# ESPEED32_V03.net
KiCad netlist of a schematic drawn in Altium Designer
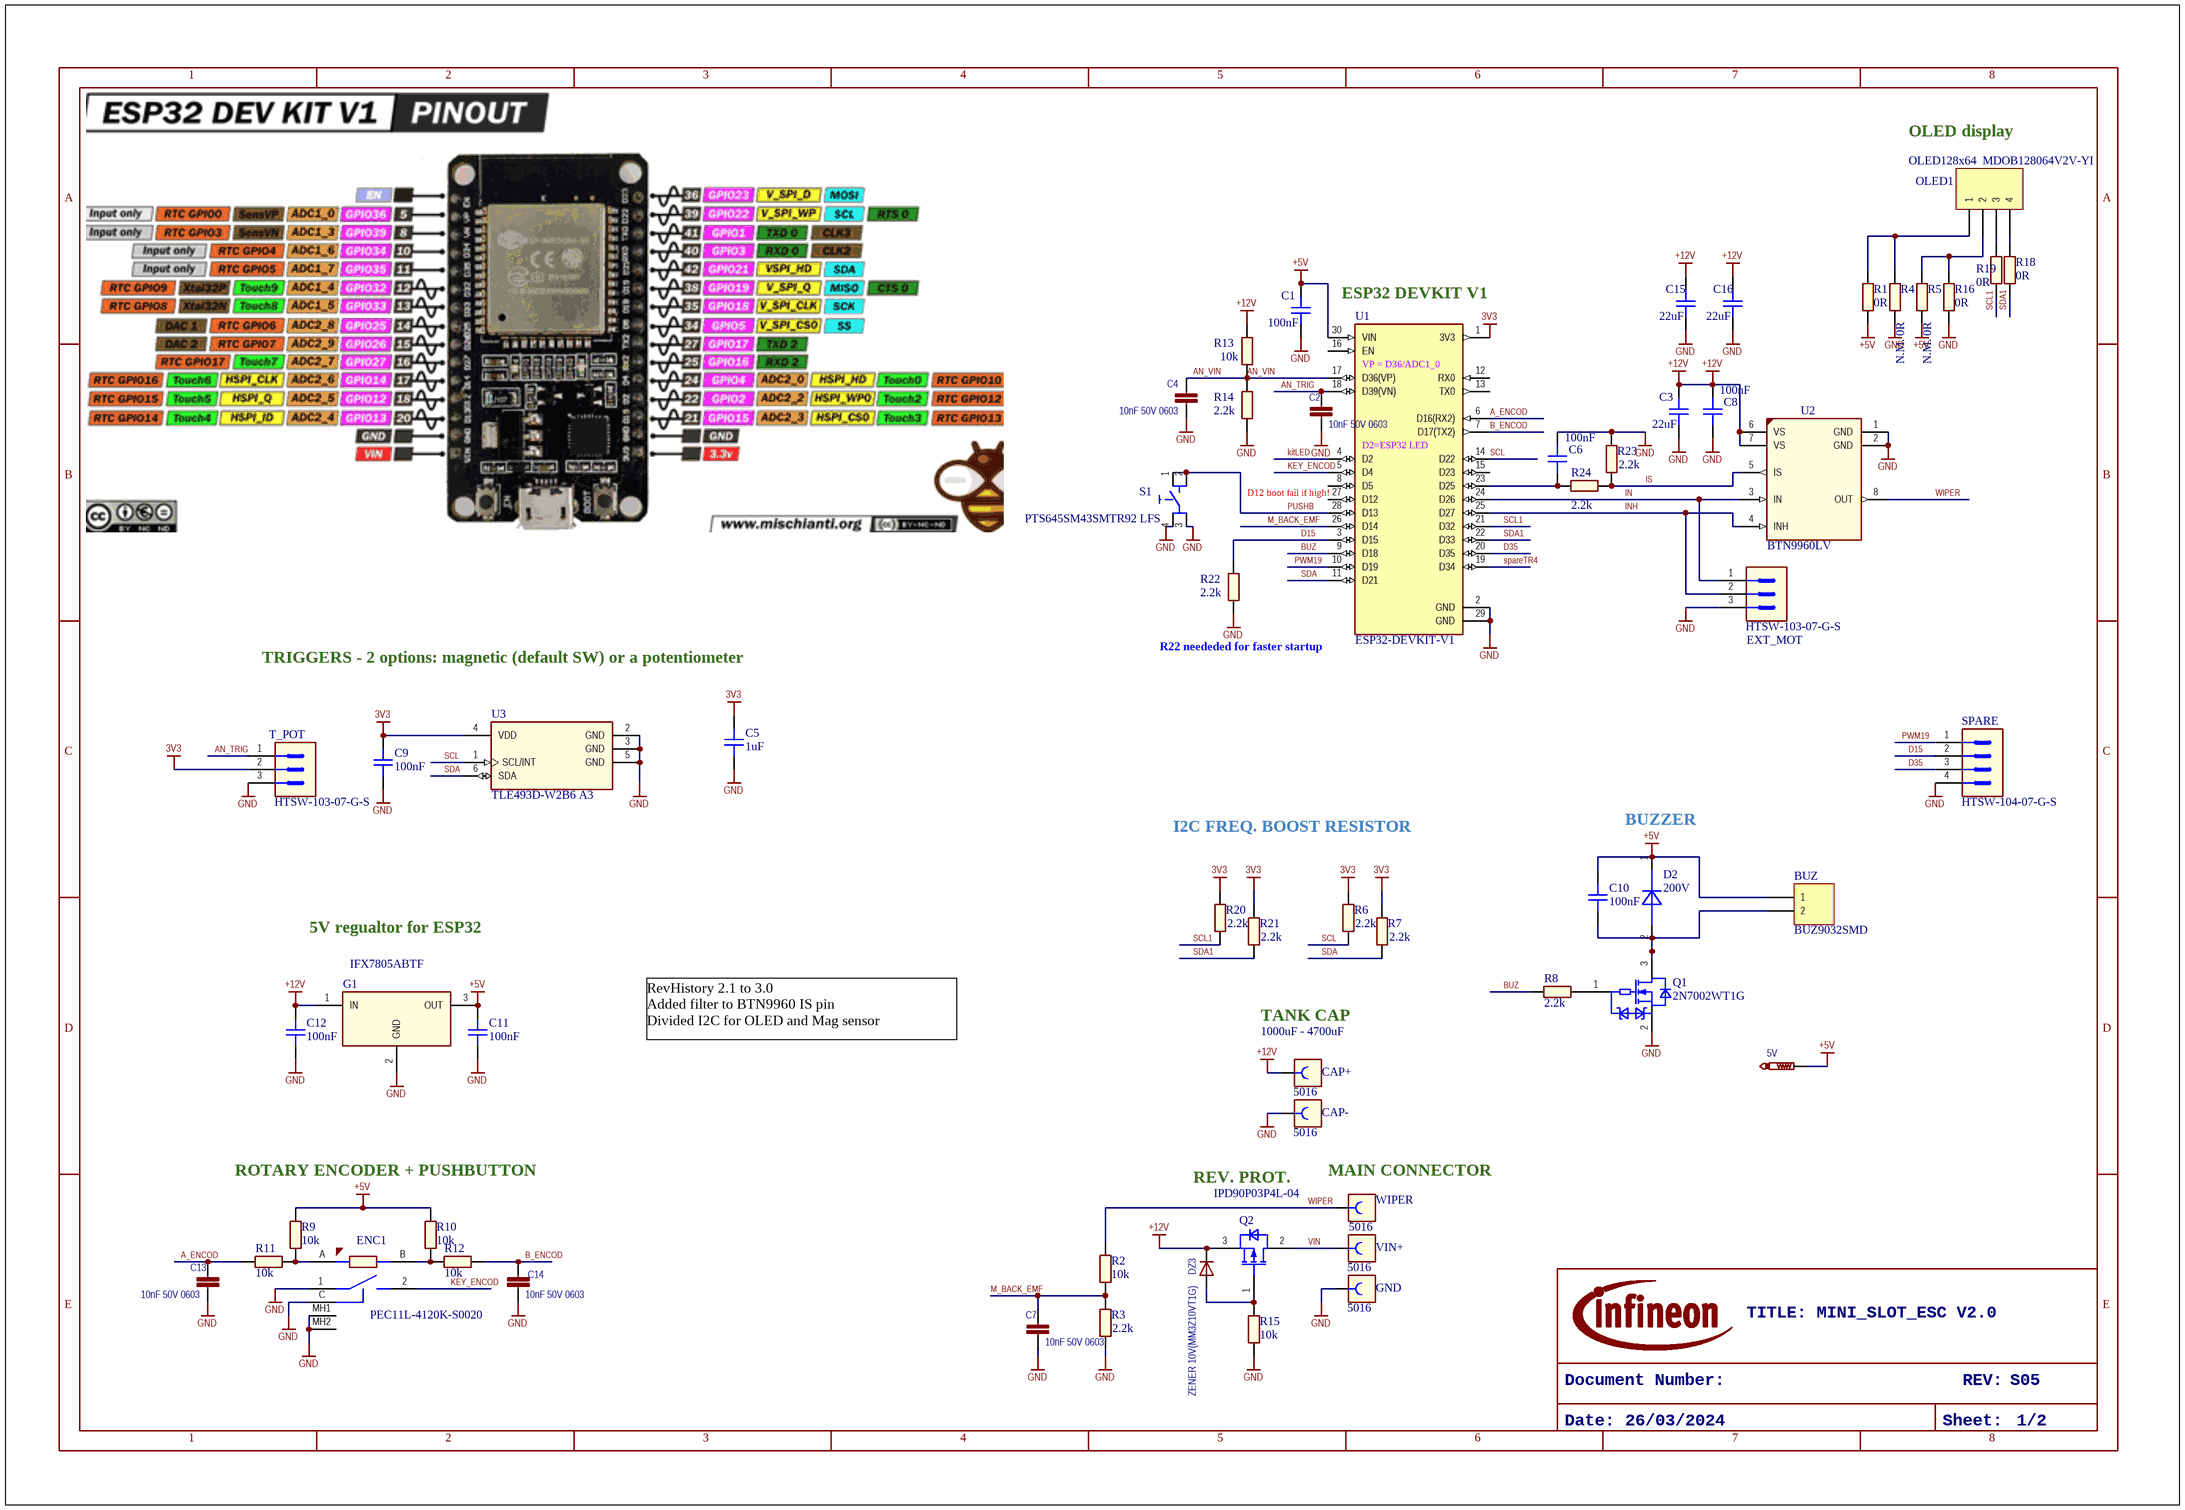
[diagram p0: ESPEED32_V03.SchDoc]

(export (version "E")
  (design (tool "Eeschema 10.0.6"))
  (components
    (comp (ref "5V")
      (value "NO_POP_Mill-Max 2501-2-00-80-00-00-07-0")
      (footprint "TEST POINT MILL-MAX 2501-2-00-80-00-00-07-0")
      (description "testpad 1mm diameter")
      (libsource (lib "LitixFlexArkasMultiChDemo3") (part "TESTPAD_1MM"))
    )
    (comp (ref "BUZ")
      (value "BUZ9032SMD")
      (footprint "MF_SLOT_ESC_V2.0:BUZ9032_SMD")
      (description "Header, 2-Pin")
      (fields (field (name "PUBLISHER") "Altium Limited"))
      (libsource (lib "Miscellaneous Connectors") (part "Header 2"))
    )
    (comp (ref "C1")
      (value "100nF")
      (footprint "C0603")
      (description "CAP / CERA / 100nF / 25V / 10% / X8R (EIA) / -55°C to 150°C / 0603(1608) / SMD / -")
      (fields (field (name "LEGACY PARTNUMBER") "CAP01008841") (field (name "MANUFACTURER") "MuRata"))
      (libsource (lib "PCBLibraryData") (part "CAP-SGL-STD-02P_00000001"))
    )
    (comp (ref "C2")
      (value "10nF 50V 0603")
      (footprint "C0603")
      (description "CAPACITOR, European symbol")
      (libsource (lib "rcl") (part "C-EUC0402"))
    )
    (comp (ref "C3")
      (value "22uF")
      (footprint "CAPC3225X270N")
      (description "CAP / CERA / 22uF / 25V / 20% / X5R (EIA) / -55°C to 85°C / 1210(3225) / SMD / -")
      (fields (field (name "LEGACY PARTNUMBER") "CAP01005898") (field (name "MANUFACTURER") "MuRata"))
      (libsource (lib "PCBLibraryData") (part "CAP-SGL-STD-02P_00000001"))
    )
    (comp (ref "C4")
      (value "10nF 50V 0603")
      (footprint "C0603")
      (description "CAPACITOR, European symbol")
      (libsource (lib "rcl") (part "C-EUC0402"))
    )
    (comp (ref "C5")
      (value "1uF")
      (footprint "CAPC1608X87N-1")
      (description "CAP / CERA / 1uF / 25V / 20% / X5R (EIA) / -55°C to 85°C / 0603(1608) / SMD / -")
      (fields (field (name "MANUFACTURER") "Wurth Elektronik"))
      (libsource (lib "PCBLibraryData") (part "CAP-SGL-STD-02P_00000001"))
    )
    (comp (ref "C6")
      (value "100nF")
      (footprint "C0603")
      (description "CAP / CERA / 100nF / 25V / 10% / X8R (EIA) / -55°C to 150°C / 0603(1608) / SMD / -")
      (fields (field (name "LEGACY PARTNUMBER") "CAP01008841") (field (name "MANUFACTURER") "MuRata"))
      (libsource (lib "PCBLibraryData") (part "CAP-SGL-STD-02P_00000001"))
    )
    (comp (ref "C7")
      (value "10nF 50V 0603")
      (footprint "C0603")
      (description "CAPACITOR, European symbol")
      (libsource (lib "rcl") (part "C-EUC0402"))
    )
    (comp (ref "C8")
      (value "100nF")
      (footprint "C0603")
      (description "CAP / CERA / 100nF / 25V / 10% / X8R (EIA) / -55°C to 150°C / 0603(1608) / SMD / -")
      (fields (field (name "LEGACY PARTNUMBER") "CAP01008841") (field (name "MANUFACTURER") "MuRata"))
      (libsource (lib "PCBLibraryData") (part "CAP-SGL-STD-02P_00000001"))
    )
    (comp (ref "C9")
      (value "100nF")
      (footprint "C0603")
      (description "CAP / CERA / 100nF / 25V / 10% / X8R (EIA) / -55°C to 150°C / 0603(1608) / SMD / -")
      (fields (field (name "LEGACY PARTNUMBER") "CAP01008841") (field (name "MANUFACTURER") "MuRata"))
      (libsource (lib "PCBLibraryData") (part "CAP-SGL-STD-02P_00000001"))
    )
    (comp (ref "C10")
      (value "100nF")
      (footprint "C0603")
      (description "CAP / CERA / 100nF / 25V / 10% / X8R (EIA) / -55°C to 150°C / 0603(1608) / SMD / -")
      (fields (field (name "LEGACY PARTNUMBER") "CAP01008841") (field (name "MANUFACTURER") "MuRata"))
      (libsource (lib "PCBLibraryData") (part "CAP-SGL-STD-02P_00000001"))
    )
    (comp (ref "C11")
      (value "100nF")
      (footprint "C0603")
      (description "CAP / CERA / 100nF / 25V / 10% / X8R (EIA) / -55°C to 150°C / 0603(1608) / SMD / -")
      (fields (field (name "LEGACY PARTNUMBER") "CAP01008841") (field (name "MANUFACTURER") "MuRata"))
      (libsource (lib "PCBLibraryData") (part "CAP-SGL-STD-02P_00000001"))
    )
    (comp (ref "C12")
      (value "100nF")
      (footprint "C0603")
      (description "CAP / CERA / 100nF / 25V / 10% / X8R (EIA) / -55°C to 150°C / 0603(1608) / SMD / -")
      (fields (field (name "LEGACY PARTNUMBER") "CAP01008841") (field (name "MANUFACTURER") "MuRata"))
      (libsource (lib "PCBLibraryData") (part "CAP-SGL-STD-02P_00000001"))
    )
    (comp (ref "C13")
      (value "10nF 50V 0603")
      (footprint "C0603")
      (description "CAPACITOR, European symbol")
      (libsource (lib "rcl") (part "C-EUC0402"))
    )
    (comp (ref "C14")
      (value "10nF 50V 0603")
      (footprint "C0603")
      (description "CAPACITOR, European symbol")
      (libsource (lib "rcl") (part "C-EUC0402"))
    )
    (comp (ref "C15")
      (value "22uF")
      (footprint "CAPC3225X270N")
      (description "CAP / CERA / 22uF / 25V / 20% / X5R (EIA) / -55°C to 85°C / 1210(3225) / SMD / -")
      (fields (field (name "LEGACY PARTNUMBER") "CAP01005898") (field (name "MANUFACTURER") "MuRata"))
      (libsource (lib "PCBLibraryData") (part "CAP-SGL-STD-02P_00000001"))
    )
    (comp (ref "C16")
      (value "22uF")
      (footprint "CAPC3225X270N")
      (description "CAP / CERA / 22uF / 25V / 20% / X5R (EIA) / -55°C to 85°C / 1210(3225) / SMD / -")
      (fields (field (name "LEGACY PARTNUMBER") "CAP01005898") (field (name "MANUFACTURER") "MuRata"))
      (libsource (lib "PCBLibraryData") (part "CAP-SGL-STD-02P_00000001"))
    )
    (comp (ref "CAP+")
      (value "5016")
      (footprint "CON-SMD-TP-5016")
      (description "Test Point, Compact, Surface Mount, Finish- Silver Plate")
      (fields
        (field (name "LEGACY PARTNUMBER") "CON01501019")
        (field (name "MANUFACTURER") "Keystone Electronics Corp.")
      )
      (libsource (lib "PCBLibraryData") (part "connector_1_f"))
    )
    (comp (ref "CAP-")
      (value "5016")
      (footprint "CON-SMD-TP-5016")
      (description "Test Point, Compact, Surface Mount, Finish- Silver Plate")
      (fields
        (field (name "LEGACY PARTNUMBER") "CON01501019")
        (field (name "MANUFACTURER") "Keystone Electronics Corp.")
      )
      (libsource (lib "PCBLibraryData") (part "connector_1_f"))
    )
    (comp (ref "D2")
      (value "200V")
      (footprint "DIO-SMD-RF05VYM2SFH")
      (description "Super Fast Recovery Diode")
      (fields (field (name "MANUFACTURER") "ROHM Semiconductors"))
      (libsource (lib "PCBLibraryData") (part "d_std_a"))
    )
    (comp (ref "DZ3")
      (value "ZENER 10V(MM3Z10VT1G)")
      (footprint "SOD323")
      (description "Zener 10V MM3Z10VST1G")
      (libsource (lib "000_Self_made_Gernot") (part "NXP_BAT46WJ"))
    )
    (comp (ref "ENC1")
      (value "PEC11L-4120K-S0020")
      (footprint "SW-THT-PEC11L-4XXXK-SXXXX")
      (description "11 mm Low Profile Encoder")
      (fields (field (name "MANUFACTURER") "Bourns"))
      (libsource (lib "PCBLibraryData") (part "PEC11L-4XXXK-SXXXX"))
    )
    (comp (ref "EXT_MOT")
      (value "HTSW-103-07-G-S")
      (footprint "CON-THT-2.54-3-1-8.38")
      (description "Through hole .025 SQ Post Header, 2.54mm pitch, 3 pin, vertical, single row")
      (fields (field (name "LEGACY PARTNUMBER") "CON00000054") (field (name "MANUFACTURER") "Samtec"))
      (libsource (lib "PCBLibraryData") (part "Header 3"))
    )
    (comp (ref "G1")
      (value "IFX7805ABTF")
      (footprint "TO228P998X235-3N-2-V")
      (description "Three Terminal 1.0A Positive Voltage Regulator")
      (fields
        (field (name "LEGACY PARTNUMBER") "IFX01400731")
        (field (name "MANUFACTURER") "Infineon Technologies")
      )
      (libsource (lib "PCBLibraryData") (part "IFX7805ABTX"))
    )
    (comp (ref "GND")
      (value "5016")
      (footprint "CON-SMD-TP-5016")
      (description "Test Point, Compact, Surface Mount, Finish- Silver Plate")
      (fields
        (field (name "LEGACY PARTNUMBER") "CON01501019")
        (field (name "MANUFACTURER") "Keystone Electronics Corp.")
      )
      (libsource (lib "PCBLibraryData") (part "connector_1_f"))
    )
    (comp (ref "OLED1")
      (value "OLED128x64  MDOB128064V2V-YI")
      (footprint "OLED 128X64 1.3\"")
      (description "Header, 4-Pin")
      (fields (field (name "PUBLISHER") "Altium Limited"))
      (libsource (lib "Miscellaneous Connectors") (part "Header 4"))
    )
    (comp (ref "Q1")
      (value "2N7002WT1G")
      (footprint "SOT65P220X100-3N")
      (fields (field (name "MANUFACTURER") "ON Semiconductor"))
      (libsource (lib "PCBLibraryData") (part "igfet_n_ch_enh_dio_r_g_esd_gs_1g2s3d_3p-2"))
    )
    (comp (ref "Q2")
      (value "IPD90P03P4L-04")
      (footprint "TO228P998X235-3N-2-V")
      (description "OptiMOS - P2 Power-Transistor, P-channel-Enhancement mode, VDS -30V")
      (fields
        (field (name "LEGACY PARTNUMBER") "IFX00200003")
        (field (name "MANUFACTURER") "Infineon Technologies")
      )
      (libsource (lib "PCBLibraryData") (part "igfet_p_ch_enh_dio_1g2d3s_3p"))
    )
    (comp (ref "R1")
      (value "0R")
      (footprint "R0603")
      (description "General Purpose Chip Resistor")
      (fields (field (name "LEGACY PARTNUMBER") "RES00000126") (field (name "MANUFACTURER") "Yageo"))
      (libsource (lib "TLD5542-1MultiCh_V4.3") (part "328011"))
    )
    (comp (ref "R2")
      (value "10k")
      (footprint "R0603")
      (description "RES / STD / 10k / 100mW / 5% / 100ppm/K / -55°C to 155°C / 0603(1608) / SMD / -")
      (fields (field (name "LEGACY PARTNUMBER") "RES01805989") (field (name "MANUFACTURER") "Yageo"))
      (libsource (lib "") (part "RES-SGL-STD-02P_00000006_1"))
    )
    (comp (ref "R3")
      (value "2.2k")
      (footprint "R0603")
      (description "RES / STD / 2.2k / 100mW / 1% / 100ppm/K / -55°C to 155°C / 0603(1608) / SMD / -")
      (fields (field (name "LEGACY PARTNUMBER") "RES00000093") (field (name "MANUFACTURER") "Yageo"))
      (libsource (lib "") (part "RES-SGL-STD-02P_00000006_1"))
    )
    (comp (ref "R4")
      (value "N.M. 0R")
      (footprint "R0603")
      (description "General Purpose Chip Resistor")
      (fields (field (name "LEGACY PARTNUMBER") "RES00000126") (field (name "MANUFACTURER") "Yageo"))
      (libsource (lib "TLD5542-1MultiCh_V4.3") (part "328011"))
    )
    (comp (ref "R5")
      (value "N.M. 0R")
      (footprint "R0603")
      (description "General Purpose Chip Resistor")
      (fields (field (name "LEGACY PARTNUMBER") "RES00000126") (field (name "MANUFACTURER") "Yageo"))
      (libsource (lib "TLD5542-1MultiCh_V4.3") (part "328011"))
    )
    (comp (ref "R6")
      (value "2.2k")
      (footprint "R0603")
      (description "RES / STD / 2.2k / 100mW / 1% / 100ppm/K / -55°C to 155°C / 0603(1608) / SMD / -")
      (fields (field (name "LEGACY PARTNUMBER") "RES00000093") (field (name "MANUFACTURER") "Yageo"))
      (libsource (lib "") (part "RES-SGL-STD-02P_00000006_1"))
    )
    (comp (ref "R7")
      (value "2.2k")
      (footprint "R0603")
      (description "RES / STD / 2.2k / 100mW / 1% / 100ppm/K / -55°C to 155°C / 0603(1608) / SMD / -")
      (fields (field (name "LEGACY PARTNUMBER") "RES00000093") (field (name "MANUFACTURER") "Yageo"))
      (libsource (lib "") (part "RES-SGL-STD-02P_00000006_1"))
    )
    (comp (ref "R8")
      (value "2.2k")
      (footprint "R0603")
      (description "RES / STD / 2.2k / 100mW / 1% / 100ppm/K / -55°C to 155°C / 0603(1608) / SMD / -")
      (fields (field (name "LEGACY PARTNUMBER") "RES00000093") (field (name "MANUFACTURER") "Yageo"))
      (libsource (lib "") (part "RES-SGL-STD-02P_00000006_2"))
    )
    (comp (ref "R9")
      (value "10k")
      (footprint "R0603")
      (description "RES / STD / 10k / 100mW / 5% / 100ppm/K / -55°C to 155°C / 0603(1608) / SMD / -")
      (fields (field (name "LEGACY PARTNUMBER") "RES01805989") (field (name "MANUFACTURER") "Yageo"))
      (libsource (lib "") (part "RES-SGL-STD-02P_00000006_1"))
    )
    (comp (ref "R10")
      (value "10k")
      (footprint "R0603")
      (description "RES / STD / 10k / 100mW / 5% / 100ppm/K / -55°C to 155°C / 0603(1608) / SMD / -")
      (fields (field (name "LEGACY PARTNUMBER") "RES01805989") (field (name "MANUFACTURER") "Yageo"))
      (libsource (lib "") (part "RES-SGL-STD-02P_00000006_1"))
    )
    (comp (ref "R11")
      (value "10k")
      (footprint "R0603")
      (description "RES / STD / 10k / 100mW / 5% / 100ppm/K / -55°C to 155°C / 0603(1608) / SMD / -")
      (fields (field (name "LEGACY PARTNUMBER") "RES01805989") (field (name "MANUFACTURER") "Yageo"))
      (libsource (lib "") (part "RES-SGL-STD-02P_00000006_2"))
    )
    (comp (ref "R12")
      (value "10k")
      (footprint "R0603")
      (description "RES / STD / 10k / 100mW / 5% / 100ppm/K / -55°C to 155°C / 0603(1608) / SMD / -")
      (fields (field (name "LEGACY PARTNUMBER") "RES01805989") (field (name "MANUFACTURER") "Yageo"))
      (libsource (lib "") (part "RES-SGL-STD-02P_00000006_2"))
    )
    (comp (ref "R13")
      (value "10k")
      (footprint "R0603")
      (description "RES / STD / 10k / 100mW / 5% / 100ppm/K / -55°C to 155°C / 0603(1608) / SMD / -")
      (fields (field (name "LEGACY PARTNUMBER") "RES01805989") (field (name "MANUFACTURER") "Yageo"))
      (libsource (lib "") (part "RES-SGL-STD-02P_00000006_1"))
    )
    (comp (ref "R14")
      (value "2.2k")
      (footprint "R0603")
      (description "RES / STD / 2.2k / 100mW / 1% / 100ppm/K / -55°C to 155°C / 0603(1608) / SMD / -")
      (fields (field (name "LEGACY PARTNUMBER") "RES00000093") (field (name "MANUFACTURER") "Yageo"))
      (libsource (lib "") (part "RES-SGL-STD-02P_00000006_1"))
    )
    (comp (ref "R15")
      (value "10k")
      (footprint "R0603")
      (description "RES / STD / 10k / 100mW / 5% / 100ppm/K / -55°C to 155°C / 0603(1608) / SMD / -")
      (fields (field (name "LEGACY PARTNUMBER") "RES01805989") (field (name "MANUFACTURER") "Yageo"))
      (libsource (lib "") (part "RES-SGL-STD-02P_00000006_1"))
    )
    (comp (ref "R16")
      (value "0R")
      (footprint "R0603")
      (description "General Purpose Chip Resistor")
      (fields (field (name "LEGACY PARTNUMBER") "RES00000126") (field (name "MANUFACTURER") "Yageo"))
      (libsource (lib "TLD5542-1MultiCh_V4.3") (part "328011"))
    )
    (comp (ref "R18")
      (value "0R")
      (footprint "R0603")
      (description "General Purpose Chip Resistor")
      (fields (field (name "LEGACY PARTNUMBER") "RES00000126") (field (name "MANUFACTURER") "Yageo"))
      (libsource (lib "TLD5542-1MultiCh_V4.3") (part "328011"))
    )
    (comp (ref "R19")
      (value "0R")
      (footprint "R0603")
      (description "General Purpose Chip Resistor")
      (fields (field (name "LEGACY PARTNUMBER") "RES00000126") (field (name "MANUFACTURER") "Yageo"))
      (libsource (lib "TLD5542-1MultiCh_V4.3") (part "328011"))
    )
    (comp (ref "R20")
      (value "2.2k")
      (footprint "R0603")
      (description "RES / STD / 2.2k / 100mW / 1% / 100ppm/K / -55°C to 155°C / 0603(1608) / SMD / -")
      (fields (field (name "LEGACY PARTNUMBER") "RES00000093") (field (name "MANUFACTURER") "Yageo"))
      (libsource (lib "") (part "RES-SGL-STD-02P_00000006_1"))
    )
    (comp (ref "R21")
      (value "2.2k")
      (footprint "R0603")
      (description "RES / STD / 2.2k / 100mW / 1% / 100ppm/K / -55°C to 155°C / 0603(1608) / SMD / -")
      (fields (field (name "LEGACY PARTNUMBER") "RES00000093") (field (name "MANUFACTURER") "Yageo"))
      (libsource (lib "") (part "RES-SGL-STD-02P_00000006_1"))
    )
    (comp (ref "R22")
      (value "2.2k")
      (footprint "R0603")
      (description "RES / STD / 2.2k / 100mW / 1% / 100ppm/K / -55°C to 155°C / 0603(1608) / SMD / -")
      (fields (field (name "LEGACY PARTNUMBER") "RES00000093") (field (name "MANUFACTURER") "Yageo"))
      (libsource (lib "") (part "RES-SGL-STD-02P_00000006_1"))
    )
    (comp (ref "R23")
      (value "2.2k")
      (footprint "R0603")
      (description "RES / STD / 2.2k / 100mW / 1% / 100ppm/K / -55°C to 155°C / 0603(1608) / SMD / -")
      (fields (field (name "LEGACY PARTNUMBER") "RES00000093") (field (name "MANUFACTURER") "Yageo"))
      (libsource (lib "") (part "RES-SGL-STD-02P_00000006_3"))
    )
    (comp (ref "R24")
      (value "2.2k")
      (footprint "R0603")
      (description "RES / STD / 2.2k / 100mW / 1% / 100ppm/K / -55°C to 155°C / 0603(1608) / SMD / -")
      (fields (field (name "LEGACY PARTNUMBER") "RES00000093") (field (name "MANUFACTURER") "Yageo"))
      (libsource (lib "PCBLibraryData") (part "RES-SGL-STD-02P_00000006"))
    )
    (comp (ref "S1")
      (value "PTS645SM43SMTR92 LFS")
      (footprint "SW-SMD-PTS645SK43SMTR92")
      (description "Tact Switches, Variety of Actuator Lengths")
      (fields (field (name "MANUFACTURER") "C&K"))
      (libsource (lib "PCBLibraryData") (part "sw_c1234_4p"))
    )
    (comp (ref "SPARE")
      (value "HTSW-104-07-G-S")
      (footprint "HDRV4W64P254_1X4_1016X248X838B")
      (description "Through hole .025 SQ Post Header, Hi-Temp Strip, 2.54mm pitch, 4 pin, vertical, single row")
      (fields (field (name "LEGACY PARTNUMBER") "CON01500246") (field (name "MANUFACTURER") "Samtec"))
      (libsource (lib "PCBLibraryData") (part "Header 4"))
    )
    (comp (ref "T_POT")
      (value "HTSW-103-07-G-S")
      (footprint "CON-THT-2.54-3-1-8.38")
      (description "Through hole .025 SQ Post Header, 2.54mm pitch, 3 pin, vertical, single row")
      (fields (field (name "LEGACY PARTNUMBER") "CON00000054") (field (name "MANUFACTURER") "Samtec"))
      (libsource (lib "PCBLibraryData") (part "Header 3"))
    )
    (comp (ref "U1")
      (value "ESP32-DEVKIT-V1")
      (footprint "MODULE_ESP32_DEVKIT_V1")
      (fields (field (name "MF") "Do it"))
      (libsource (lib "ESP32-DEVKIT-V1") (part "ESP32-DEVKIT-V1"))
    )
    (comp (ref "U2")
      (value "BTN9960LV")
      (footprint "IFX-PG-HSOF-7-1-V")
      (description "MOTIX Single Half-Bridge with Integrated Driver IC")
      (fields (field (name "MANUFACTURER") "Infineon Technologies"))
      (libsource (lib "PCBLibraryData") (part "BTN99X0LV"))
    )
    (comp (ref "U3")
      (value "TLE493D-W2B6 A3")
      (footprint "SOP95P280X110-6N-V")
      (description "Low Power 3D Hall Sensor with I2C Interface and Wake Up Function, Temp Range(-40 to 125°C)")
      (fields (field (name "MANUFACTURER") "Infineon Technologies"))
      (libsource (lib "PCBLibraryData") (part "TLE493D-W2B6"))
    )
    (comp (ref "VIN+")
      (value "5016")
      (footprint "CON-SMD-TP-5016")
      (description "Test Point, Compact, Surface Mount, Finish- Silver Plate")
      (fields
        (field (name "LEGACY PARTNUMBER") "CON01501019")
        (field (name "MANUFACTURER") "Keystone Electronics Corp.")
      )
      (libsource (lib "PCBLibraryData") (part "connector_1_f"))
    )
    (comp (ref "WIPER")
      (value "5016")
      (footprint "CON-SMD-TP-5016")
      (description "Test Point, Compact, Surface Mount, Finish- Silver Plate")
      (fields
        (field (name "LEGACY PARTNUMBER") "CON01501019")
        (field (name "MANUFACTURER") "Keystone Electronics Corp.")
      )
      (libsource (lib "PCBLibraryData") (part "connector_1_f"))
    )
  )
  (nets
    (net (code "1") (name "+5V") (class "Default")
      (node (ref "5V") (pin "1") (pinfunction "TP_1") (pintype "passive"))
      (node (ref "BUZ") (pin "1") (pinfunction "1_1") (pintype "passive"))
      (node (ref "C1") (pin "2") (pinfunction "2_2") (pintype "passive"))
      (node (ref "C10") (pin "2") (pinfunction "2_2") (pintype "passive"))
      (node (ref "C11") (pin "2") (pinfunction "2_2") (pintype "passive"))
      (node (ref "D2") (pin "1") (pinfunction "Cathode_1") (pintype "passive"))
      (node (ref "G1") (pin "3") (pinfunction "OUT_3") (pintype "power_in"))
      (node (ref "R1") (pin "1") (pinfunction "1_1") (pintype "passive"))
      (node (ref "R10") (pin "2") (pinfunction "2_2") (pintype "passive"))
      (node (ref "R5") (pin "1") (pinfunction "1_1") (pintype "passive"))
      (node (ref "R9") (pin "2") (pinfunction "2_2") (pintype "passive"))
      (node (ref "U1") (pin "30") (pinfunction "VIN_30") (pintype "input"))
    )
    (net (code "2") (name "+12V") (class "Default")
      (node (ref "C12") (pin "2") (pinfunction "2_2") (pintype "passive"))
      (node (ref "C15") (pin "2") (pinfunction "2_2") (pintype "passive"))
      (node (ref "C16") (pin "2") (pinfunction "2_2") (pintype "passive"))
      (node (ref "C3") (pin "2") (pinfunction "2_2") (pintype "passive"))
      (node (ref "C8") (pin "2") (pinfunction "2_2") (pintype "passive"))
      (node (ref "CAP+") (pin "1") (pinfunction "1_1") (pintype "passive"))
      (node (ref "DZ3") (pin "K") (pinfunction "K_K") (pintype "passive"))
      (node (ref "G1") (pin "1") (pinfunction "IN_1") (pintype "power_in"))
      (node (ref "Q2") (pin "3") (pinfunction "SOURCE_3") (pintype "passive"))
      (node (ref "R13") (pin "2") (pinfunction "2_2") (pintype "passive"))
      (node (ref "U2") (pin "6") (pinfunction "VS_6") (pintype "power_in"))
      (node (ref "U2") (pin "7") (pinfunction "VS_7") (pintype "power_in"))
    )
    (net (code "3") (name "/AN_TRIG") (class "Default")
      (node (ref "C2") (pin "2") (pinfunction "2_2") (pintype "passive"))
      (node (ref "T_POT") (pin "1") (pinfunction "1_1") (pintype "passive"))
      (node (ref "U1") (pin "18") (pinfunction "D39(VN)_18") (pintype "bidirectional"))
    )
    (net (code "4") (name "/AN_VIN") (class "Default")
      (node (ref "C4") (pin "2") (pinfunction "2_2") (pintype "passive"))
      (node (ref "R13") (pin "1") (pinfunction "1_1") (pintype "passive"))
      (node (ref "R14") (pin "2") (pinfunction "2_2") (pintype "passive"))
      (node (ref "U1") (pin "17") (pinfunction "D36(VP)_17") (pintype "bidirectional"))
    )
    (net (code "5") (name "/A_ENCOD") (class "Default")
      (node (ref "C13") (pin "2") (pinfunction "2_2") (pintype "passive"))
      (node (ref "R11") (pin "2") (pinfunction "2_2") (pintype "passive"))
      (node (ref "U1") (pin "6") (pinfunction "D16(RX2)_6") (pintype "input"))
    )
    (net (code "6") (name "/BUZ") (class "Default")
      (node (ref "R8") (pin "2") (pinfunction "2_2") (pintype "passive"))
      (node (ref "U1") (pin "9") (pinfunction "D18_9") (pintype "bidirectional"))
    )
    (net (code "7") (name "/B_ENCOD") (class "Default")
      (node (ref "C14") (pin "2") (pinfunction "2_2") (pintype "passive"))
      (node (ref "R12") (pin "1") (pinfunction "1_1") (pintype "passive"))
      (node (ref "U1") (pin "7") (pinfunction "D17(TX2)_7") (pintype "output"))
    )
    (net (code "8") (name "/D15") (class "Default")
      (node (ref "R22") (pin "2") (pinfunction "2_2") (pintype "passive"))
      (node (ref "SPARE") (pin "2") (pinfunction "2_2") (pintype "passive"))
      (node (ref "U1") (pin "3") (pinfunction "D15_3") (pintype "bidirectional"))
    )
    (net (code "9") (name "/D35") (class "Default")
      (node (ref "SPARE") (pin "3") (pinfunction "3_3") (pintype "passive"))
      (node (ref "U1") (pin "20") (pinfunction "D35_20") (pintype "bidirectional"))
    )
    (net (code "10") (name "/IN") (class "Default")
      (node (ref "EXT_MOT") (pin "1") (pinfunction "1_1") (pintype "passive"))
      (node (ref "U1") (pin "24") (pinfunction "D26_24") (pintype "bidirectional"))
      (node (ref "U2") (pin "3") (pinfunction "IN_3") (pintype "input"))
    )
    (net (code "11") (name "/INH") (class "Default")
      (node (ref "EXT_MOT") (pin "2") (pinfunction "2_2") (pintype "passive"))
      (node (ref "U1") (pin "25") (pinfunction "D27_25") (pintype "bidirectional"))
      (node (ref "U2") (pin "4") (pinfunction "INH_4") (pintype "input"))
    )
    (net (code "12") (name "/IS") (class "Default")
      (node (ref "R23") (pin "2") (pinfunction "2_2") (pintype "passive"))
      (node (ref "R24") (pin "2") (pinfunction "2_2") (pintype "passive"))
      (node (ref "U2") (pin "5") (pinfunction "IS_5") (pintype "output"))
    )
    (net (code "13") (name "/KEY_ENCOD") (class "Default")
      (node (ref "ENC1") (pin "2") (pinfunction "2_2") (pintype "passive"))
      (node (ref "U1") (pin "5") (pinfunction "D4_5") (pintype "bidirectional"))
    )
    (net (code "14") (name "/M_BACK_EMF") (class "Default")
      (node (ref "C7") (pin "2") (pinfunction "2_2") (pintype "passive"))
      (node (ref "R2") (pin "1") (pinfunction "1_1") (pintype "passive"))
      (node (ref "R3") (pin "2") (pinfunction "2_2") (pintype "passive"))
      (node (ref "U1") (pin "26") (pinfunction "D14_26") (pintype "bidirectional"))
    )
    (net (code "15") (name "/PUSHB") (class "Default")
      (node (ref "S1") (pin "1") (pintype "passive"))
      (node (ref "S1") (pin "2") (pintype "passive"))
      (node (ref "U1") (pin "28") (pinfunction "D13_28") (pintype "bidirectional"))
    )
    (net (code "16") (name "/PWM19") (class "Default")
      (node (ref "SPARE") (pin "1") (pinfunction "1_1") (pintype "passive"))
      (node (ref "U1") (pin "10") (pinfunction "D19_10") (pintype "bidirectional"))
    )
    (net (code "17") (name "/SCL") (class "Default")
      (node (ref "R6") (pin "1") (pinfunction "1_1") (pintype "passive"))
      (node (ref "U1") (pin "14") (pinfunction "D22_14") (pintype "bidirectional"))
      (node (ref "U3") (pin "1") (pinfunction "SCL/INT_1") (pintype "input"))
    )
    (net (code "18") (name "/SCL1") (class "Default")
      (node (ref "R19") (pin "1") (pinfunction "1_1") (pintype "passive"))
      (node (ref "R20") (pin "1") (pinfunction "1_1") (pintype "passive"))
      (node (ref "U1") (pin "21") (pinfunction "D32_21") (pintype "bidirectional"))
    )
    (net (code "19") (name "/SDA") (class "Default")
      (node (ref "R7") (pin "1") (pinfunction "1_1") (pintype "passive"))
      (node (ref "U1") (pin "11") (pinfunction "D21_11") (pintype "bidirectional"))
      (node (ref "U3") (pin "6") (pinfunction "SDA_6") (pintype "bidirectional"))
    )
    (net (code "20") (name "/SDA1") (class "Default")
      (node (ref "R18") (pin "1") (pinfunction "1_1") (pintype "passive"))
      (node (ref "R21") (pin "1") (pinfunction "1_1") (pintype "passive"))
      (node (ref "U1") (pin "22") (pinfunction "D33_22") (pintype "bidirectional"))
    )
    (net (code "21") (name "/VIN") (class "Default")
      (node (ref "Q2") (pin "2") (pinfunction "DRAIN_2") (pintype "passive"))
      (node (ref "VIN+") (pin "1") (pinfunction "1_1") (pintype "passive"))
    )
    (net (code "22") (name "/WIPER") (class "Default")
      (node (ref "R2") (pin "2") (pinfunction "2_2") (pintype "passive"))
      (node (ref "U2") (pin "8") (pinfunction "OUT_8") (pintype "output"))
      (node (ref "WIPER") (pin "1") (pinfunction "1_1") (pintype "passive"))
    )
    (net (code "23") (name "/kitLED") (class "Default")
      (node (ref "U1") (pin "4") (pinfunction "D2_4") (pintype "bidirectional"))
    )
    (net (code "24") (name "/spareTR4") (class "Default")
      (node (ref "U1") (pin "19") (pinfunction "D34_19") (pintype "bidirectional"))
    )
    (net (code "25") (name "3V3") (class "Default")
      (node (ref "C5") (pin "2") (pinfunction "2_2") (pintype "passive"))
      (node (ref "C9") (pin "2") (pinfunction "2_2") (pintype "passive"))
      (node (ref "R20") (pin "2") (pinfunction "2_2") (pintype "passive"))
      (node (ref "R21") (pin "2") (pinfunction "2_2") (pintype "passive"))
      (node (ref "R6") (pin "2") (pinfunction "2_2") (pintype "passive"))
      (node (ref "R7") (pin "2") (pinfunction "2_2") (pintype "passive"))
      (node (ref "T_POT") (pin "2") (pinfunction "2_2") (pintype "passive"))
      (node (ref "U1") (pin "1") (pinfunction "3V3_1") (pintype "output"))
      (node (ref "U3") (pin "4") (pinfunction "VDD_4") (pintype "power_in"))
    )
    (net (code "26") (name "GND") (class "Default")
      (node (ref "C1") (pin "1") (pinfunction "1_1") (pintype "passive"))
      (node (ref "C11") (pin "1") (pinfunction "1_1") (pintype "passive"))
      (node (ref "C12") (pin "1") (pinfunction "1_1") (pintype "passive"))
      (node (ref "C13") (pin "1") (pinfunction "1_1") (pintype "passive"))
      (node (ref "C14") (pin "1") (pinfunction "1_1") (pintype "passive"))
      (node (ref "C15") (pin "1") (pinfunction "1_1") (pintype "passive"))
      (node (ref "C16") (pin "1") (pinfunction "1_1") (pintype "passive"))
      (node (ref "C2") (pin "1") (pinfunction "1_1") (pintype "passive"))
      (node (ref "C3") (pin "1") (pinfunction "1_1") (pintype "passive"))
      (node (ref "C4") (pin "1") (pinfunction "1_1") (pintype "passive"))
      (node (ref "C5") (pin "1") (pinfunction "1_1") (pintype "passive"))
      (node (ref "C6") (pin "2") (pinfunction "2_2") (pintype "passive"))
      (node (ref "C7") (pin "1") (pinfunction "1_1") (pintype "passive"))
      (node (ref "C8") (pin "1") (pinfunction "1_1") (pintype "passive"))
      (node (ref "C9") (pin "1") (pinfunction "1_1") (pintype "passive"))
      (node (ref "CAP-") (pin "1") (pinfunction "1_1") (pintype "passive"))
      (node (ref "ENC1") (pin "1") (pinfunction "1_1") (pintype "passive"))
      (node (ref "ENC1") (pin "C") (pinfunction "C_C") (pintype "passive"))
      (node (ref "ENC1") (pin "MH1") (pinfunction "MH1_MH1") (pintype "passive"))
      (node (ref "ENC1") (pin "MH2") (pinfunction "MH2_MH2") (pintype "passive"))
      (node (ref "EXT_MOT") (pin "3") (pinfunction "3_3") (pintype "passive"))
      (node (ref "G1") (pin "2") (pinfunction "GND_2") (pintype "power_in"))
      (node (ref "GND") (pin "1") (pinfunction "1_1") (pintype "passive"))
      (node (ref "Q1") (pin "2") (pinfunction "S_2") (pintype "passive"))
      (node (ref "R14") (pin "1") (pinfunction "1_1") (pintype "passive"))
      (node (ref "R15") (pin "1") (pinfunction "1_1") (pintype "passive"))
      (node (ref "R16") (pin "1") (pinfunction "1_1") (pintype "passive"))
      (node (ref "R22") (pin "1") (pinfunction "1_1") (pintype "passive"))
      (node (ref "R23") (pin "1") (pinfunction "1_1") (pintype "passive"))
      (node (ref "R3") (pin "1") (pinfunction "1_1") (pintype "passive"))
      (node (ref "R4") (pin "1") (pinfunction "1_1") (pintype "passive"))
      (node (ref "S1") (pin "3") (pintype "passive"))
      (node (ref "S1") (pin "4") (pintype "passive"))
      (node (ref "SPARE") (pin "4") (pinfunction "4_4") (pintype "passive"))
      (node (ref "T_POT") (pin "3") (pinfunction "3_3") (pintype "passive"))
      (node (ref "U1") (pin "2") (pinfunction "GND_2") (pintype "power_in"))
      (node (ref "U1") (pin "29") (pinfunction "GND_29") (pintype "power_in"))
      (node (ref "U2") (pin "1") (pinfunction "GND_1") (pintype "power_in"))
      (node (ref "U2") (pin "2") (pinfunction "GND_2") (pintype "power_in"))
      (node (ref "U3") (pin "2") (pinfunction "GND_2") (pintype "power_in"))
      (node (ref "U3") (pin "3") (pinfunction "GND_3") (pintype "power_in"))
      (node (ref "U3") (pin "5") (pinfunction "GND_5") (pintype "power_in"))
    )
    (net (code "27") (name "Net-(D2-Anode)") (class "Default")
      (node (ref "BUZ") (pin "2") (pinfunction "2_2") (pintype "passive"))
      (node (ref "C10") (pin "1") (pinfunction "1_1") (pintype "passive"))
      (node (ref "D2") (pin "2") (pinfunction "Anode_2") (pintype "passive"))
      (node (ref "Q1") (pin "3") (pinfunction "D_3") (pintype "passive"))
    )
    (net (code "28") (name "Net-(ENC1-PadA)") (class "Default")
      (node (ref "ENC1") (pin "A") (pinfunction "A_A") (pintype "passive"))
      (node (ref "R11") (pin "1") (pinfunction "1_1") (pintype "passive"))
      (node (ref "R9") (pin "1") (pinfunction "1_1") (pintype "passive"))
    )
    (net (code "29") (name "Net-(ENC1-PadB)") (class "Default")
      (node (ref "ENC1") (pin "B") (pinfunction "B_B") (pintype "passive"))
      (node (ref "R10") (pin "1") (pinfunction "1_1") (pintype "passive"))
      (node (ref "R12") (pin "2") (pinfunction "2_2") (pintype "passive"))
    )
    (net (code "30") (name "Net-(OLED1-Pad1)") (class "Default")
      (node (ref "OLED1") (pin "1") (pinfunction "1_1") (pintype "passive"))
      (node (ref "R1") (pin "2") (pinfunction "2_2") (pintype "passive"))
      (node (ref "R4") (pin "2") (pinfunction "2_2") (pintype "passive"))
    )
    (net (code "31") (name "Net-(OLED1-Pad2)") (class "Default")
      (node (ref "OLED1") (pin "2") (pinfunction "2_2") (pintype "passive"))
      (node (ref "R16") (pin "2") (pinfunction "2_2") (pintype "passive"))
      (node (ref "R5") (pin "2") (pinfunction "2_2") (pintype "passive"))
    )
    (net (code "32") (name "Net-(OLED1-Pad3)") (class "Default")
      (node (ref "OLED1") (pin "3") (pinfunction "3_3") (pintype "passive"))
      (node (ref "R19") (pin "2") (pinfunction "2_2") (pintype "passive"))
    )
    (net (code "33") (name "Net-(OLED1-Pad4)") (class "Default")
      (node (ref "OLED1") (pin "4") (pinfunction "4_4") (pintype "passive"))
      (node (ref "R18") (pin "2") (pinfunction "2_2") (pintype "passive"))
    )
    (net (code "34") (name "Net-(Q1-G)") (class "Default")
      (node (ref "Q1") (pin "1") (pinfunction "G_1") (pintype "passive"))
      (node (ref "R8") (pin "1") (pinfunction "1_1") (pintype "passive"))
    )
    (net (code "35") (name "Net-(Q2-GATE)") (class "Default")
      (node (ref "DZ3") (pin "A") (pinfunction "A_A") (pintype "passive"))
      (node (ref "Q2") (pin "1") (pinfunction "GATE_1") (pintype "passive"))
      (node (ref "R15") (pin "2") (pinfunction "2_2") (pintype "passive"))
    )
    (net (code "36") (name "Net-(U1-D25)") (class "Default")
      (node (ref "C6") (pin "1") (pinfunction "1_1") (pintype "passive"))
      (node (ref "R24") (pin "1") (pinfunction "1_1") (pintype "passive"))
      (node (ref "U1") (pin "23") (pinfunction "D25_23") (pintype "bidirectional"))
    )
    (net (code "37") (name "unconnected-(U1-D5-Pad8)") (class "Default")
      (node (ref "U1") (pin "8") (pinfunction "D5_8") (pintype "bidirectional"))
    )
    (net (code "38") (name "unconnected-(U1-D12-Pad27)") (class "Default")
      (node (ref "U1") (pin "27") (pinfunction "D12_27") (pintype "bidirectional"))
    )
    (net (code "39") (name "unconnected-(U1-D23-Pad15)") (class "Default")
      (node (ref "U1") (pin "15") (pinfunction "D23_15") (pintype "bidirectional"))
    )
    (net (code "40") (name "unconnected-(U1-EN-Pad16)") (class "Default")
      (node (ref "U1") (pin "16") (pinfunction "EN_16") (pintype "input"))
    )
    (net (code "41") (name "unconnected-(U1-RX0-Pad12)") (class "Default")
      (node (ref "U1") (pin "12") (pinfunction "RX0_12") (pintype "input"))
    )
    (net (code "42") (name "unconnected-(U1-TX0-Pad13)") (class "Default")
      (node (ref "U1") (pin "13") (pinfunction "TX0_13") (pintype "output"))
    )
  )
)
